# PSU.net
KiCad netlist of a schematic drawn in Altium Designer
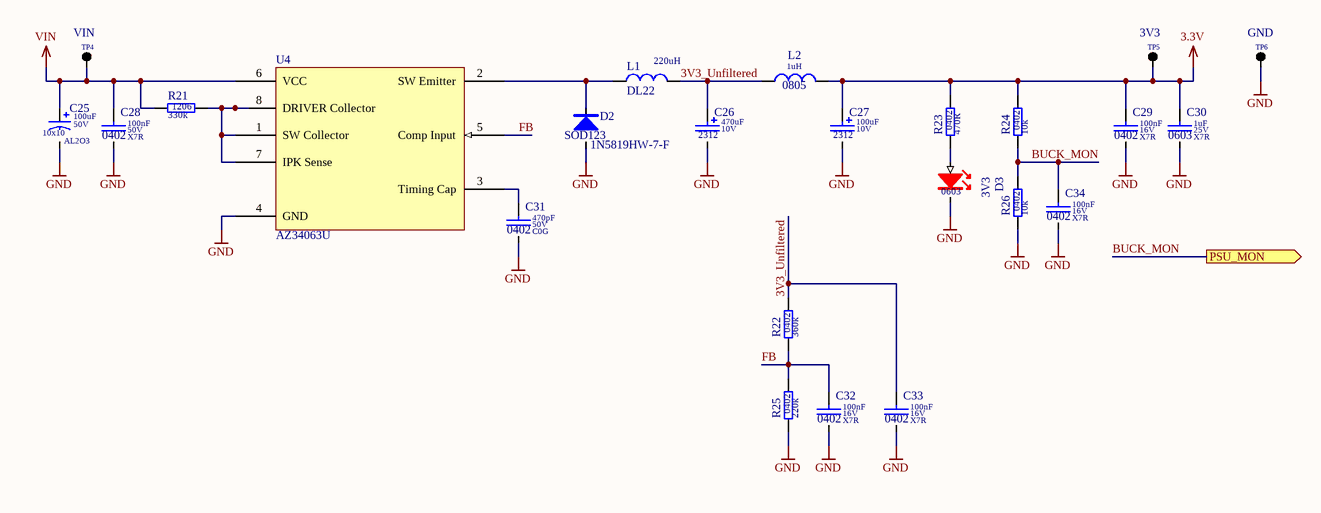
[diagram p0: PSU.SchDoc]

(export (version "E")
  (design (tool "Eeschema 10.0.6"))
  (components
    (comp (ref "C25")
      (value "100uF")
      (footprint "CE_D_10x10MM")
      (description "Polarized Capacitor")
      (fields
        (field (name "DIELECTRIC") "AL2O3")
        (field (name "SCH_FOOTPRINT") "10x10")
        (field (name "VOLTAGE") "50V")
        (field (name "PART NUMBER") "CE_100uF_50V_AL2O3_10x10_20")
        (field (name "MANUFACTURER") "Nichicon")
      )
      (libsource (lib "Library") (part "CE"))
    )
    (comp (ref "C26")
      (value "470uF")
      (footprint "CT_2312_6032")
      (description "Capacitor")
      (fields
        (field (name "SCH_FOOTPRINT") "2312")
        (field (name "VOLTAGE") "10V")
        (field (name "PART NUMBER") "CT_22uF_16V_TA2O5_2312_10")
        (field (name "MANUFACTURER") "Kemet")
      )
      (libsource (lib "Library") (part "CT"))
    )
    (comp (ref "C27")
      (value "100uF")
      (footprint "CT_2312_6032")
      (description "Capacitor")
      (fields
        (field (name "SCH_FOOTPRINT") "2312")
        (field (name "VOLTAGE") "10V")
        (field (name "PART NUMBER") "CT_22uF_16V_TA2O5_2312_10")
        (field (name "MANUFACTURER") "Kemet")
      )
      (libsource (lib "Library") (part "CT"))
    )
    (comp (ref "C28")
      (value "100nF")
      (footprint "C_0402_1005")
      (description "Capacitor")
      (fields
        (field (name "DIELECTRIC") "X7R")
        (field (name "VOLTAGE") "50V")
        (field (name "SCH_FOOTPRINT") "0402")
        (field (name "PART NUMBER") "C_100nF_50V_X7R_0402_10")
        (field (name "MANUFACTURER") "Murata")
      )
      (libsource (lib "Library") (part "C"))
    )
    (comp (ref "C29")
      (value "100nF")
      (footprint "C_0402_1005")
      (description "Capacitor")
      (fields
        (field (name "DIELECTRIC") "X7R")
        (field (name "VOLTAGE") "16V")
        (field (name "SCH_FOOTPRINT") "0402")
        (field (name "PART NUMBER") "C_100nF_16V_X7R_0402_10")
        (field (name "MANUFACTURER") "Murata")
      )
      (libsource (lib "Library") (part "C"))
    )
    (comp (ref "C30")
      (value "1uF")
      (footprint "C_0603_1608")
      (description "Capacitor")
      (fields
        (field (name "DIELECTRIC") "X7R")
        (field (name "VOLTAGE") "25V")
        (field (name "SCH_FOOTPRINT") "0603")
        (field (name "PART NUMBER") "C_1uF_25V_X7R_0603_10")
        (field (name "MANUFACTURER") "Samsung")
      )
      (libsource (lib "Library") (part "C"))
    )
    (comp (ref "C31")
      (value "470pF")
      (footprint "C_0402_1005")
      (description "Capacitor")
      (fields
        (field (name "DIELECTRIC") "C0G")
        (field (name "VOLTAGE") "50V")
        (field (name "SCH_FOOTPRINT") "0402")
        (field (name "PART NUMBER") "C_470pF_50V_C0G_0402_5")
        (field (name "MANUFACTURER") "AVX")
      )
      (libsource (lib "Library") (part "C"))
    )
    (comp (ref "C32")
      (value "100nF")
      (footprint "C_0402_1005")
      (description "Capacitor")
      (fields
        (field (name "DIELECTRIC") "X7R")
        (field (name "VOLTAGE") "16V")
        (field (name "SCH_FOOTPRINT") "0402")
        (field (name "PART NUMBER") "C_100nF_16V_X7R_0402_10")
        (field (name "MANUFACTURER") "Murata")
      )
      (libsource (lib "Library") (part "C"))
    )
    (comp (ref "C33")
      (value "100nF")
      (footprint "C_0402_1005")
      (description "Capacitor")
      (fields
        (field (name "DIELECTRIC") "X7R")
        (field (name "VOLTAGE") "16V")
        (field (name "SCH_FOOTPRINT") "0402")
        (field (name "PART NUMBER") "C_100nF_16V_X7R_0402_10")
        (field (name "MANUFACTURER") "Murata")
      )
      (libsource (lib "Library") (part "C"))
    )
    (comp (ref "C34")
      (value "100nF")
      (footprint "C_0402_1005")
      (description "Capacitor")
      (fields
        (field (name "DIELECTRIC") "X7R")
        (field (name "VOLTAGE") "16V")
        (field (name "SCH_FOOTPRINT") "0402")
        (field (name "PART NUMBER") "C_100nF_16V_X7R_0402_10")
        (field (name "MANUFACTURER") "Murata")
      )
      (libsource (lib "Library") (part "C"))
    )
    (comp (ref "D2")
      (value "1N5819HW-7-F")
      (footprint "SOD123")
      (fields
        (field (name "SCH_FOOTPRINT") "SOD123")
        (field (name "PART NUMBER") "D_1N5819HW_1A_40V_SOD123")
        (field (name "VOLTAGE") "40V")
        (field (name "MANUFACTURER") "Diodes Inc")
      )
      (libsource (lib "Library") (part "D"))
    )
    (comp (ref "D3")
      (value "3V3")
      (footprint "OL_0603_1608")
      (description "LED_RED")
      (fields
        (field (name "SCH_FOOTPRINT") "0603")
        (field (name "PART NUMBER") "OL_R_0603")
        (field (name "MANUFACTURER") "Lite-On")
      )
      (libsource (lib "Library") (part "OL_R"))
    )
    (comp (ref "L1")
      (value "DL22")
      (footprint "DL22")
      (description "Dławik: drutowy; SMD; 1uH; Ipracy: 7,1A; 8mΩ; Isat: 7,6A; B: 9,4mm")
      (fields (field (name "ALTIUM_VALUE") "220uH"))
      (libsource (lib "Lib - Passives") (part "DL22"))
    )
    (comp (ref "L2")
      (value "1uH")
      (footprint "L_0805_2012")
      (description "Induction")
      (fields
        (field (name "SCH_FOOTPRINT") "0805")
        (field (name "PART NUMBER") "NL05KTC1R0")
        (field (name "MANUFACTURER") "VIKING")
      )
      (libsource (lib "Library") (part "L"))
    )
    (comp (ref "R21")
      (value "330k")
      (footprint "R_1206_3216")
      (fields
        (field (name "SCH_FOOTPRINT") "1206")
        (field (name "PART NUMBER") "R_330k_1206_1")
        (field (name "VOLTAGE") "200V")
        (field (name "POWER") "250mW")
      )
      (libsource (lib "Library") (part "R"))
    )
    (comp (ref "R22")
      (value "360k")
      (footprint "R_0402_1005")
      (fields
        (field (name "SCH_FOOTPRINT") "0402")
        (field (name "PART NUMBER") "R_360R_0402_1")
        (field (name "VOLTAGE") "50V")
        (field (name "POWER") "63mW")
      )
      (libsource (lib "Library") (part "R"))
    )
    (comp (ref "R23")
      (value "470R")
      (footprint "R_0402_1005")
      (fields
        (field (name "SCH_FOOTPRINT") "0402")
        (field (name "PART NUMBER") "R_470R_0402_1")
        (field (name "VOLTAGE") "50V")
        (field (name "POWER") "63mW")
      )
      (libsource (lib "Library") (part "R"))
    )
    (comp (ref "R24")
      (value "10k")
      (footprint "R_0402_1005")
      (fields
        (field (name "SCH_FOOTPRINT") "0402")
        (field (name "PART NUMBER") "R_10k_0402_1")
        (field (name "VOLTAGE") "50V")
        (field (name "POWER") "63mW")
      )
      (libsource (lib "Library") (part "R"))
    )
    (comp (ref "R25")
      (value "220k")
      (footprint "R_0402_1005")
      (fields
        (field (name "SCH_FOOTPRINT") "0402")
        (field (name "PART NUMBER") "R_220k_0402_1")
        (field (name "VOLTAGE") "50V")
        (field (name "POWER") "63mW")
      )
      (libsource (lib "Library") (part "R"))
    )
    (comp (ref "R26")
      (value "10k")
      (footprint "R_0402_1005")
      (fields
        (field (name "SCH_FOOTPRINT") "0402")
        (field (name "PART NUMBER") "R_10k_0402_1")
        (field (name "VOLTAGE") "50V")
        (field (name "POWER") "63mW")
      )
      (libsource (lib "Library") (part "R"))
    )
    (comp (ref "TP4")
      (value "VIN")
      (footprint "TP_PAD")
      (description "Testpoint")
      (fields (field (name "PART NUMBER") "TP_PAD"))
      (libsource (lib "Library") (part "TP_TESTPOINT"))
    )
    (comp (ref "TP5")
      (value "3V3")
      (footprint "TP_PAD")
      (description "Testpoint")
      (fields (field (name "PART NUMBER") "TP_PAD"))
      (libsource (lib "Library") (part "TP_TESTPOINT"))
    )
    (comp (ref "TP6")
      (value "GND")
      (footprint "TP_PAD")
      (description "Testpoint")
      (fields (field (name "PART NUMBER") "TP_PAD"))
      (libsource (lib "Library") (part "TP_TESTPOINT"))
    )
    (comp (ref "U4")
      (value "AZ34063U")
      (footprint "AZ34063UMTR-G1")
      (description "IC: PMIC; przetwornica DC/DC; Uwej: 3÷36VDC; Uwyj: 1,25÷36VDC; 1,5A")
      (libsource (lib "Lib - Voltage Regulators") (part "AZ34063UMTR-G1"))
    )
  )
  (nets
    (net (code "1") (name "/3V3_Unfiltered") (class "Default")
      (node (ref "C26") (pin "1") (pinfunction "1_1") (pintype "passive"))
      (node (ref "C33") (pin "1") (pinfunction "1_1") (pintype "passive"))
      (node (ref "L1") (pin "1") (pinfunction "1_1") (pintype "passive"))
      (node (ref "L2") (pin "1") (pinfunction "1_1") (pintype "passive"))
      (node (ref "R22") (pin "2") (pinfunction "2_2") (pintype "passive"))
    )
    (net (code "2") (name "/BUCK_MON") (class "Default")
      (node (ref "C34") (pin "1") (pinfunction "1_1") (pintype "passive"))
      (node (ref "R24") (pin "1") (pinfunction "1_1") (pintype "passive"))
      (node (ref "R26") (pin "2") (pinfunction "2_2") (pintype "passive"))
    )
    (net (code "3") (name "/FB") (class "Default")
      (node (ref "C32") (pin "1") (pinfunction "1_1") (pintype "passive"))
      (node (ref "R22") (pin "1") (pinfunction "1_1") (pintype "passive"))
      (node (ref "R25") (pin "2") (pinfunction "2_2") (pintype "passive"))
      (node (ref "U4") (pin "5") (pinfunction "Comp_Input_5") (pintype "input"))
    )
    (net (code "4") (name "3.3V") (class "Default")
      (node (ref "C27") (pin "1") (pinfunction "1_1") (pintype "passive"))
      (node (ref "C29") (pin "1") (pinfunction "1_1") (pintype "passive"))
      (node (ref "C30") (pin "1") (pinfunction "1_1") (pintype "passive"))
      (node (ref "L2") (pin "2") (pinfunction "2_2") (pintype "passive"))
      (node (ref "R23") (pin "2") (pinfunction "2_2") (pintype "passive"))
      (node (ref "R24") (pin "2") (pinfunction "2_2") (pintype "passive"))
      (node (ref "TP5") (pin "1") (pinfunction "TP_1") (pintype "passive"))
    )
    (net (code "5") (name "GND") (class "Default")
      (node (ref "C25") (pin "2") (pinfunction "2_2") (pintype "passive"))
      (node (ref "C26") (pin "2") (pinfunction "2_2") (pintype "passive"))
      (node (ref "C27") (pin "2") (pinfunction "2_2") (pintype "passive"))
      (node (ref "C28") (pin "2") (pinfunction "2_2") (pintype "passive"))
      (node (ref "C29") (pin "2") (pinfunction "2_2") (pintype "passive"))
      (node (ref "C30") (pin "2") (pinfunction "2_2") (pintype "passive"))
      (node (ref "C31") (pin "2") (pinfunction "2_2") (pintype "passive"))
      (node (ref "C32") (pin "2") (pinfunction "2_2") (pintype "passive"))
      (node (ref "C33") (pin "2") (pinfunction "2_2") (pintype "passive"))
      (node (ref "C34") (pin "2") (pinfunction "2_2") (pintype "passive"))
      (node (ref "D2") (pin "2") (pintype "passive"))
      (node (ref "D3") (pin "1") (pinfunction "K_1") (pintype "output"))
      (node (ref "R25") (pin "1") (pinfunction "1_1") (pintype "passive"))
      (node (ref "R26") (pin "1") (pinfunction "1_1") (pintype "passive"))
      (node (ref "TP6") (pin "1") (pinfunction "TP_1") (pintype "passive"))
      (node (ref "U4") (pin "4") (pinfunction "GND_4") (pintype "power_in"))
    )
    (net (code "6") (name "Net-(D3-A)") (class "Default")
      (node (ref "D3") (pin "2") (pinfunction "A_2") (pintype "input"))
      (node (ref "R23") (pin "1") (pinfunction "1_1") (pintype "passive"))
    )
    (net (code "7") (name "Net-(U4-DRIVER_Collector)") (class "Default")
      (node (ref "R21") (pin "2") (pinfunction "2_2") (pintype "passive"))
      (node (ref "U4") (pin "1") (pinfunction "SW_Collector_1") (pintype "passive"))
      (node (ref "U4") (pin "7") (pinfunction "IPK_Sense_7") (pintype "passive"))
      (node (ref "U4") (pin "8") (pinfunction "DRIVER_Collector_8") (pintype "passive"))
    )
    (net (code "8") (name "Net-(U4-SW_Emitter)") (class "Default")
      (node (ref "D2") (pin "1") (pintype "passive"))
      (node (ref "L1") (pin "2") (pinfunction "2_2") (pintype "passive"))
      (node (ref "U4") (pin "2") (pinfunction "SW_Emitter_2") (pintype "passive"))
    )
    (net (code "9") (name "Net-(U4-Timing_Cap)") (class "Default")
      (node (ref "C31") (pin "1") (pinfunction "1_1") (pintype "passive"))
      (node (ref "U4") (pin "3") (pinfunction "Timing_Cap_3") (pintype "passive"))
    )
    (net (code "10") (name "VIN") (class "Default")
      (node (ref "C25") (pin "1") (pinfunction "1_1") (pintype "passive"))
      (node (ref "C28") (pin "1") (pinfunction "1_1") (pintype "passive"))
      (node (ref "R21") (pin "1") (pinfunction "1_1") (pintype "passive"))
      (node (ref "TP4") (pin "1") (pinfunction "TP_1") (pintype "passive"))
      (node (ref "U4") (pin "6") (pinfunction "VCC_6") (pintype "power_in"))
    )
  )
)
